# lt8471.net
KiCad netlist of a schematic drawn in EAGLE
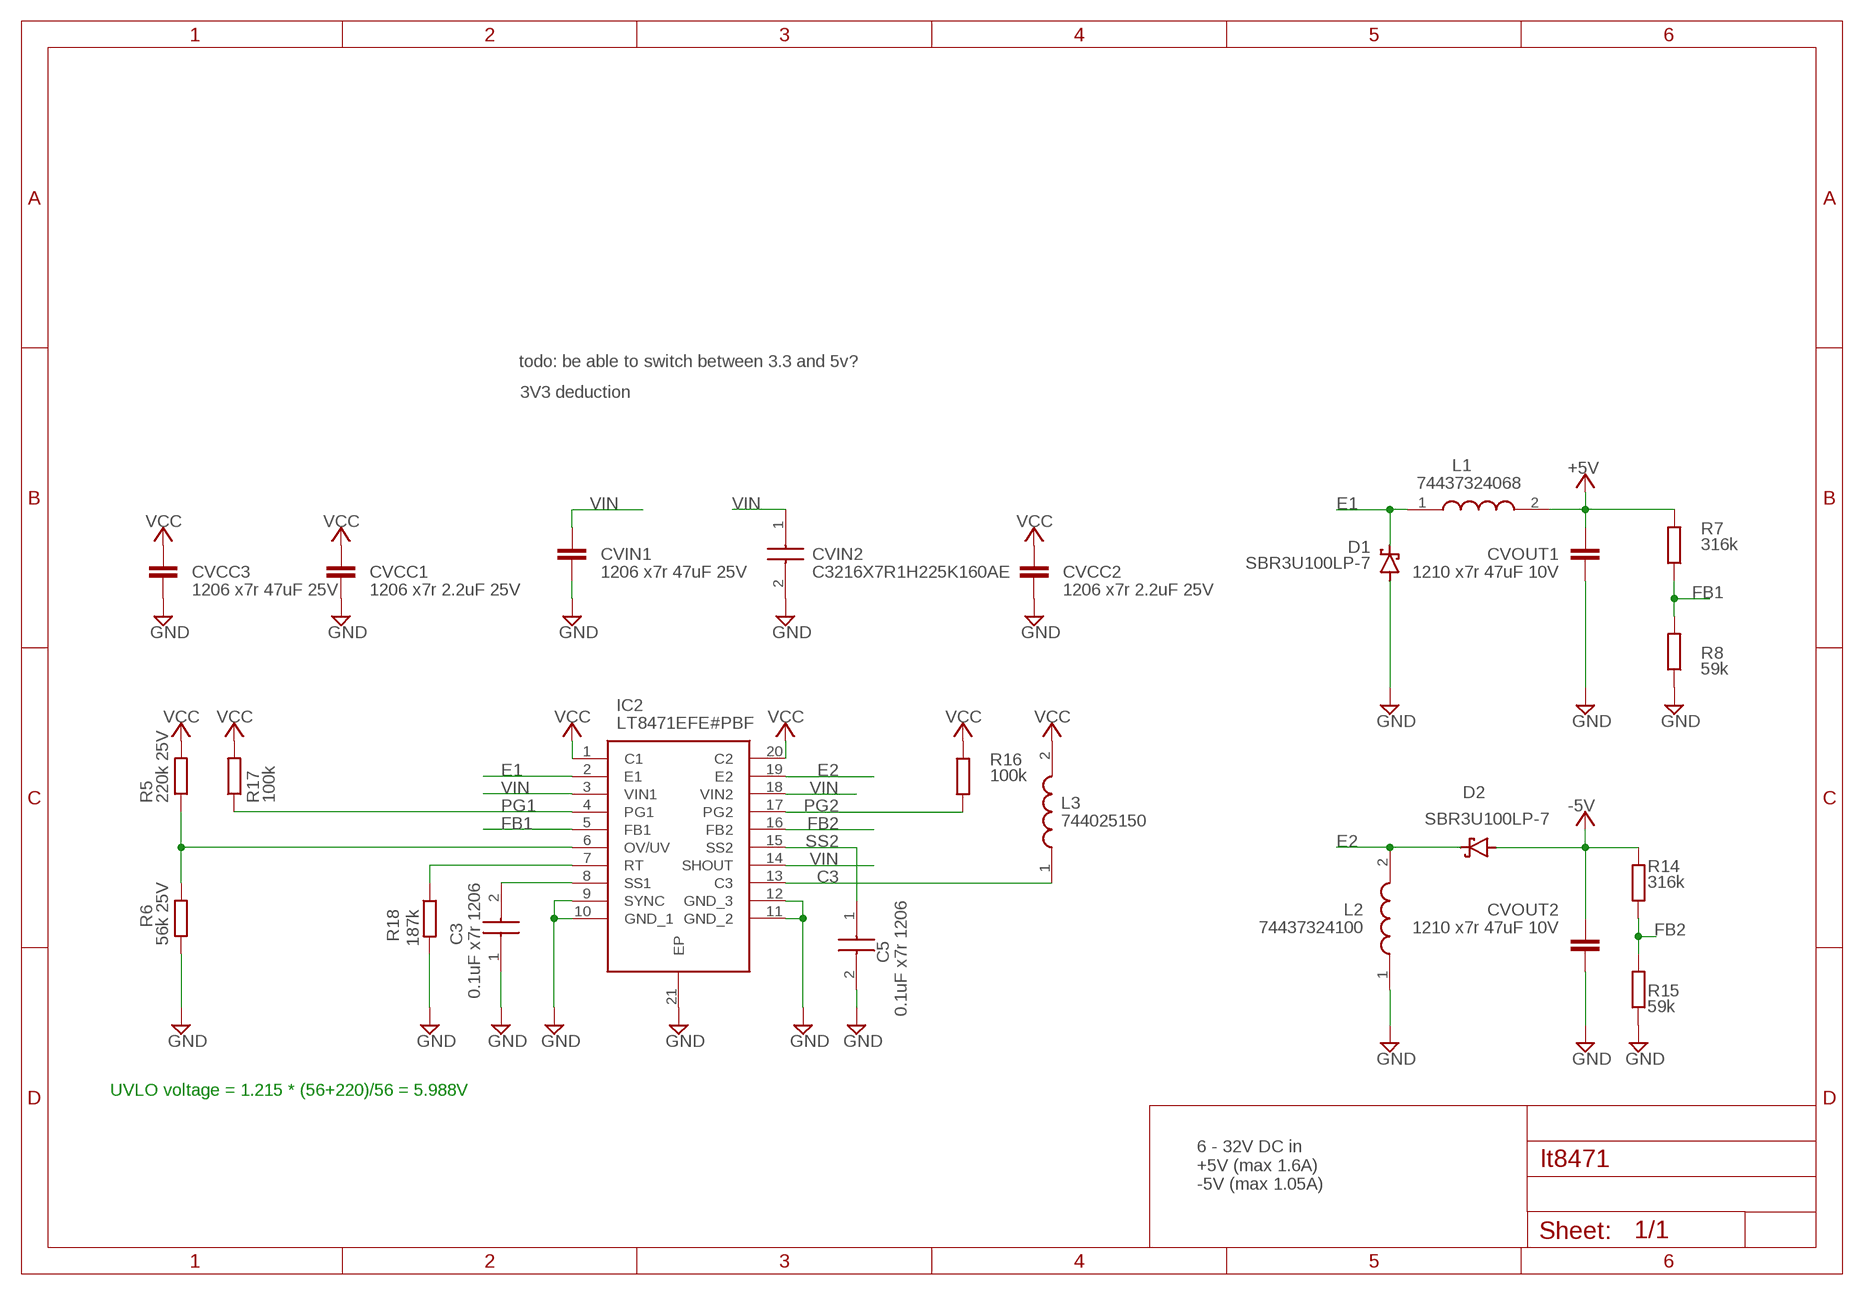
[diagram p0: schematic, sheet 1]

(export (version "E")
  (design (tool "Eeschema 10.0.6"))
  (components
    (comp (ref "C3")
      (value "0.1uF x7r 1206")
      (footprint "eagle-import:CAPC3416X90N")
      (fields (field (name "MANUFACTURER_PART_NUMBER") "MCSH31B104K500CT"))
      (libsource (lib "eagle-import") (part "MCSH31B104K500CT"))
    )
    (comp (ref "C5")
      (value "0.1uF x7r 1206")
      (footprint "eagle-import:CAPC3416X90N")
      (fields (field (name "MANUFACTURER_PART_NUMBER") "MCSH31B104K500CT"))
      (libsource (lib "eagle-import") (part "MCSH31B104K500CT"))
    )
    (comp (ref "CVCC1")
      (value "1206 x7r 2.2uF 25V")
      (footprint "eagle-import:C1206")
      (libsource (lib "eagle-import") (part "C-EUC1206"))
    )
    (comp (ref "CVCC2")
      (value "1206 x7r 2.2uF 25V")
      (footprint "eagle-import:C1206")
      (libsource (lib "eagle-import") (part "C-EUC1206"))
    )
    (comp (ref "CVCC3")
      (value "1206 x7r 47uF 25V")
      (footprint "eagle-import:C1210")
      (libsource (lib "eagle-import") (part "C-EUC1210"))
    )
    (comp (ref "CVIN1")
      (value "1206 x7r 47uF 25V")
      (footprint "eagle-import:C1210")
      (libsource (lib "eagle-import") (part "C-EUC1210"))
    )
    (comp (ref "CVIN2")
      (value "C3216X7R1H225K160AE")
      (footprint "eagle-import:CAPC3216X180N")
      (fields (field (name "MOUSER_PART_NUMBER") "810-C3216X7R1H225KST"))
      (libsource (lib "eagle-import") (part "C3216X7R1H225K160AE"))
    )
    (comp (ref "CVOUT1")
      (value "1210 x7r 47uF 10V")
      (footprint "eagle-import:C1210")
      (libsource (lib "eagle-import") (part "C-EUC1210"))
    )
    (comp (ref "CVOUT2")
      (value "1210 x7r 47uF 10V")
      (footprint "eagle-import:C1210")
      (libsource (lib "eagle-import") (part "C-EUC1210"))
    )
    (comp (ref "D1")
      (value "SBR3U100LP-7")
      (footprint "eagle-import:SBR3U100LP7")
      (fields
        (field (name "MOUSER_PART_NUMBER") "621-SBR3U100LP-7")
        (field (name "RS_PART_NUMBER") "8855599P")
      )
      (libsource (lib "eagle-import") (part "SBR3U100LP-7"))
    )
    (comp (ref "D2")
      (value "SBR3U100LP-7")
      (footprint "eagle-import:SBR3U100LP7")
      (fields
        (field (name "MOUSER_PART_NUMBER") "621-SBR3U100LP-7")
        (field (name "RS_PART_NUMBER") "8855599P")
      )
      (libsource (lib "eagle-import") (part "SBR3U100LP-7"))
    )
    (comp (ref "IC2")
      (value "LT8471EFE#PBF")
      (footprint "eagle-import:SOP65P640X120-21N")
      (fields
        (field (name "MOUSER_PART_NUMBER") "584-LT8471EFE#PBF")
        (field (name "RS_PART_NUMBER") "1513320")
      )
      (libsource (lib "eagle-import") (part "LT8471EFE#PBF"))
    )
    (comp (ref "L1")
      (value "74437324068")
      (footprint "eagle-import:WE-LHMI_402048")
      (fields
        (field (name "MOUSER_PART_NUMBER") "710-74437324068")
        (field (name "RS_PART_NUMBER") "7568480P")
      )
      (libsource (lib "eagle-import") (part "74437324068"))
    )
    (comp (ref "L2")
      (value "74437324100")
      (footprint "eagle-import:WE-LHMI_402048")
      (fields
        (field (name "MOUSER_PART_NUMBER") "710-74437324100")
        (field (name "RS_PART_NUMBER") "7568487P")
      )
      (libsource (lib "eagle-import") (part "74437324100"))
    )
    (comp (ref "L3")
      (value "744025150")
      (footprint "eagle-import:WE-TPC_282892")
      (fields (field (name "MOUSER_PART_NUMBER") "710-744025150") (field (name "RS_PART_NUMBER") "7373639P"))
      (libsource (lib "eagle-import") (part "744025150"))
    )
    (comp (ref "R5")
      (value "220k 25V")
      (footprint "eagle-import:M1206")
      (libsource (lib "eagle-import") (part "resistor_348_R-EU_M1206"))
    )
    (comp (ref "R6")
      (value "56k 25V")
      (footprint "eagle-import:M1206")
      (libsource (lib "eagle-import") (part "resistor_348_R-EU_M1206"))
    )
    (comp (ref "R7")
      (value "316k")
      (footprint "eagle-import:R1206")
      (libsource (lib "eagle-import") (part "R-EU_R1206"))
    )
    (comp (ref "R8")
      (value "59k")
      (footprint "eagle-import:R1206")
      (libsource (lib "eagle-import") (part "R-EU_R1206"))
    )
    (comp (ref "R14")
      (value "316k")
      (footprint "eagle-import:R1206")
      (libsource (lib "eagle-import") (part "R-EU_R1206"))
    )
    (comp (ref "R15")
      (value "59k")
      (footprint "eagle-import:R1206")
      (libsource (lib "eagle-import") (part "R-EU_R1206"))
    )
    (comp (ref "R16")
      (value "100k")
      (footprint "eagle-import:R1206")
      (libsource (lib "eagle-import") (part "R-EU_R1206"))
    )
    (comp (ref "R17")
      (value "100k")
      (footprint "eagle-import:R1206")
      (libsource (lib "eagle-import") (part "R-EU_R1206"))
    )
    (comp (ref "R18")
      (value "187k")
      (footprint "eagle-import:R1206")
      (libsource (lib "eagle-import") (part "R-EU_R1206"))
    )
  )
  (nets
    (net (code "1") (name "+5V") (class "Default")
      (node (ref "CVOUT1") (pin "2") (pinfunction "2_2") (pintype "passive"))
      (node (ref "L1") (pin "2") (pinfunction "2_2") (pintype "bidirectional"))
      (node (ref "R7") (pin "2") (pinfunction "2_2") (pintype "passive"))
    )
    (net (code "2") (name "-5V") (class "Default")
      (node (ref "CVOUT2") (pin "2") (pinfunction "2_2") (pintype "passive"))
      (node (ref "D2") (pin "1") (pinfunction "A_1") (pintype "passive"))
      (node (ref "D2") (pin "2") (pinfunction "A_2") (pintype "passive"))
      (node (ref "D2") (pin "3") (pinfunction "A_3") (pintype "passive"))
      (node (ref "D2") (pin "4") (pinfunction "A_4") (pintype "passive"))
      (node (ref "R14") (pin "2") (pinfunction "2_2") (pintype "passive"))
    )
    (net (code "3") (name "/C3") (class "Default")
      (node (ref "IC2") (pin "13") (pinfunction "C3_13") (pintype "bidirectional"))
      (node (ref "L3") (pin "1") (pinfunction "1_1") (pintype "bidirectional"))
    )
    (net (code "4") (name "/E1") (class "Default")
      (node (ref "D1") (pin "5") (pinfunction "C_5") (pintype "passive"))
      (node (ref "IC2") (pin "2") (pinfunction "E1_2") (pintype "bidirectional"))
      (node (ref "L1") (pin "1") (pinfunction "1_1") (pintype "bidirectional"))
    )
    (net (code "5") (name "/E2") (class "Default")
      (node (ref "D2") (pin "5") (pinfunction "C_5") (pintype "passive"))
      (node (ref "IC2") (pin "19") (pinfunction "E2_19") (pintype "bidirectional"))
      (node (ref "L2") (pin "2") (pinfunction "2_2") (pintype "bidirectional"))
    )
    (net (code "6") (name "/FB1") (class "Default")
      (node (ref "IC2") (pin "5") (pinfunction "FB1_5") (pintype "bidirectional"))
      (node (ref "R7") (pin "1") (pinfunction "1_1") (pintype "passive"))
      (node (ref "R8") (pin "2") (pinfunction "2_2") (pintype "passive"))
    )
    (net (code "7") (name "/FB2") (class "Default")
      (node (ref "IC2") (pin "16") (pinfunction "FB2_16") (pintype "bidirectional"))
      (node (ref "R14") (pin "1") (pinfunction "1_1") (pintype "passive"))
      (node (ref "R15") (pin "2") (pinfunction "2_2") (pintype "passive"))
    )
    (net (code "8") (name "/PG1") (class "Default")
      (node (ref "IC2") (pin "4") (pinfunction "PG1_4") (pintype "bidirectional"))
      (node (ref "R17") (pin "1") (pinfunction "1_1") (pintype "passive"))
    )
    (net (code "9") (name "/PG2") (class "Default")
      (node (ref "IC2") (pin "17") (pinfunction "PG2_17") (pintype "bidirectional"))
      (node (ref "R16") (pin "2") (pinfunction "2_2") (pintype "passive"))
    )
    (net (code "10") (name "/SS2") (class "Default")
      (node (ref "C5") (pin "1") (pinfunction "1_1") (pintype "bidirectional"))
      (node (ref "IC2") (pin "15") (pinfunction "SS2_15") (pintype "bidirectional"))
    )
    (net (code "11") (name "/VIN") (class "Default")
      (node (ref "CVIN1") (pin "1") (pinfunction "1_1") (pintype "passive"))
      (node (ref "CVIN2") (pin "1") (pinfunction "1_1") (pintype "bidirectional"))
      (node (ref "IC2") (pin "14") (pinfunction "SHOUT_14") (pintype "bidirectional"))
      (node (ref "IC2") (pin "18") (pinfunction "VIN2_18") (pintype "bidirectional"))
      (node (ref "IC2") (pin "3") (pinfunction "VIN1_3") (pintype "bidirectional"))
    )
    (net (code "12") (name "GND") (class "Default")
      (node (ref "C3") (pin "1") (pinfunction "1_1") (pintype "bidirectional"))
      (node (ref "C5") (pin "2") (pinfunction "2_2") (pintype "bidirectional"))
      (node (ref "CVCC1") (pin "2") (pinfunction "2_2") (pintype "passive"))
      (node (ref "CVCC2") (pin "1") (pinfunction "1_1") (pintype "passive"))
      (node (ref "CVCC3") (pin "1") (pinfunction "1_1") (pintype "passive"))
      (node (ref "CVIN1") (pin "2") (pinfunction "2_2") (pintype "passive"))
      (node (ref "CVIN2") (pin "2") (pinfunction "2_2") (pintype "bidirectional"))
      (node (ref "CVOUT1") (pin "1") (pinfunction "1_1") (pintype "passive"))
      (node (ref "CVOUT2") (pin "1") (pinfunction "1_1") (pintype "passive"))
      (node (ref "D1") (pin "1") (pinfunction "A_1") (pintype "passive"))
      (node (ref "D1") (pin "2") (pinfunction "A_2") (pintype "passive"))
      (node (ref "D1") (pin "3") (pinfunction "A_3") (pintype "passive"))
      (node (ref "D1") (pin "4") (pinfunction "A_4") (pintype "passive"))
      (node (ref "IC2") (pin "10") (pinfunction "GND_1_10") (pintype "bidirectional"))
      (node (ref "IC2") (pin "11") (pinfunction "GND_2_11") (pintype "bidirectional"))
      (node (ref "IC2") (pin "12") (pinfunction "GND_3_12") (pintype "bidirectional"))
      (node (ref "IC2") (pin "21") (pinfunction "EP_21") (pintype "bidirectional"))
      (node (ref "IC2") (pin "9") (pinfunction "SYNC_9") (pintype "bidirectional"))
      (node (ref "L2") (pin "1") (pinfunction "1_1") (pintype "bidirectional"))
      (node (ref "R15") (pin "1") (pinfunction "1_1") (pintype "passive"))
      (node (ref "R18") (pin "2") (pinfunction "2_2") (pintype "passive"))
      (node (ref "R6") (pin "1") (pinfunction "1_1") (pintype "passive"))
      (node (ref "R8") (pin "1") (pinfunction "1_1") (pintype "passive"))
    )
    (net (code "13") (name "Net-(IC2-OV{slash}UV)") (class "Default")
      (node (ref "IC2") (pin "6") (pinfunction "OV/UV_6") (pintype "bidirectional"))
      (node (ref "R5") (pin "1") (pinfunction "1_1") (pintype "passive"))
      (node (ref "R6") (pin "2") (pinfunction "2_2") (pintype "passive"))
    )
    (net (code "14") (name "Net-(IC2-RT)") (class "Default")
      (node (ref "IC2") (pin "7") (pinfunction "RT_7") (pintype "bidirectional"))
      (node (ref "R18") (pin "1") (pinfunction "1_1") (pintype "passive"))
    )
    (net (code "15") (name "Net-(IC2-SS1)") (class "Default")
      (node (ref "C3") (pin "2") (pinfunction "2_2") (pintype "bidirectional"))
      (node (ref "IC2") (pin "8") (pinfunction "SS1_8") (pintype "bidirectional"))
    )
    (net (code "16") (name "VCC") (class "Default")
      (node (ref "CVCC1") (pin "1") (pinfunction "1_1") (pintype "passive"))
      (node (ref "CVCC2") (pin "2") (pinfunction "2_2") (pintype "passive"))
      (node (ref "CVCC3") (pin "2") (pinfunction "2_2") (pintype "passive"))
      (node (ref "IC2") (pin "1") (pinfunction "C1_1") (pintype "bidirectional"))
      (node (ref "IC2") (pin "20") (pinfunction "C2_20") (pintype "bidirectional"))
      (node (ref "L3") (pin "2") (pinfunction "2_2") (pintype "bidirectional"))
      (node (ref "R16") (pin "1") (pinfunction "1_1") (pintype "passive"))
      (node (ref "R17") (pin "2") (pinfunction "2_2") (pintype "passive"))
      (node (ref "R5") (pin "2") (pinfunction "2_2") (pintype "passive"))
    )
  )
)
